# band_pass_filter.net
KiCad netlist of a schematic drawn in Altium Designer
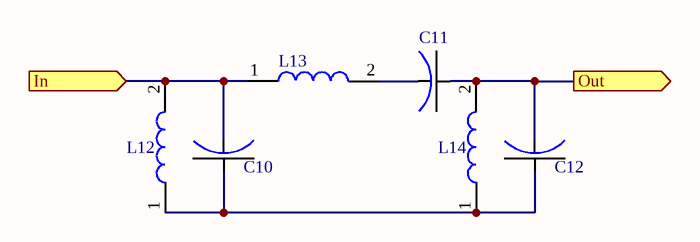
[diagram p0: band_pass_filter.SchDoc]

(export (version "E")
  (design (tool "Eeschema 10.0.6"))
  (components
    (comp (ref "C10") (value "Cap") (footprint "C2225") (libsource (lib "Integrated_Library1") (part "Cap")))
    (comp (ref "C11") (value "Cap") (footprint "C1812") (libsource (lib "Integrated_Library1") (part "Cap")))
    (comp (ref "C12") (value "Cap") (footprint "C2225") (libsource (lib "Integrated_Library1") (part "Cap")))
    (comp (ref "L12")
      (value "L1008")
      (footprint "L1008")
      (description "Vishay IMC1008E2RJ7")
      (libsource (lib "Integrated_Library1") (part "L1008"))
    )
    (comp (ref "L13")
      (value "L1008")
      (footprint "L1008")
      (description "Vishay IMC1008E2RJ7")
      (libsource (lib "Integrated_Library1") (part "L1008"))
    )
    (comp (ref "L14")
      (value "L1008")
      (footprint "L1008")
      (description "Vishay IMC1008E2RJ7")
      (libsource (lib "Integrated_Library1") (part "L1008"))
    )
  )
  (nets
    (net (code "1") (name "/In") (class "Default")
      (node (ref "C10") (pin "1") (pinfunction "1_1") (pintype "passive"))
      (node (ref "L12") (pin "2") (pinfunction "2_2") (pintype "passive"))
      (node (ref "L13") (pin "1") (pinfunction "1_1") (pintype "passive"))
    )
    (net (code "2") (name "/Out") (class "Default")
      (node (ref "C11") (pin "2") (pinfunction "2_2") (pintype "passive"))
      (node (ref "C12") (pin "1") (pinfunction "1_1") (pintype "passive"))
      (node (ref "L14") (pin "2") (pinfunction "2_2") (pintype "passive"))
    )
    (net (code "3") (name "Net-(C10-Pad2)") (class "Default")
      (node (ref "C10") (pin "2") (pinfunction "2_2") (pintype "passive"))
      (node (ref "C12") (pin "2") (pinfunction "2_2") (pintype "passive"))
      (node (ref "L12") (pin "1") (pinfunction "1_1") (pintype "passive"))
      (node (ref "L14") (pin "1") (pinfunction "1_1") (pintype "passive"))
    )
    (net (code "4") (name "Net-(C11-Pad1)") (class "Default")
      (node (ref "C11") (pin "1") (pinfunction "1_1") (pintype "passive"))
      (node (ref "L13") (pin "2") (pinfunction "2_2") (pintype "passive"))
    )
  )
)
